# STM32.net
KiCad netlist of a schematic drawn in Altium Designer
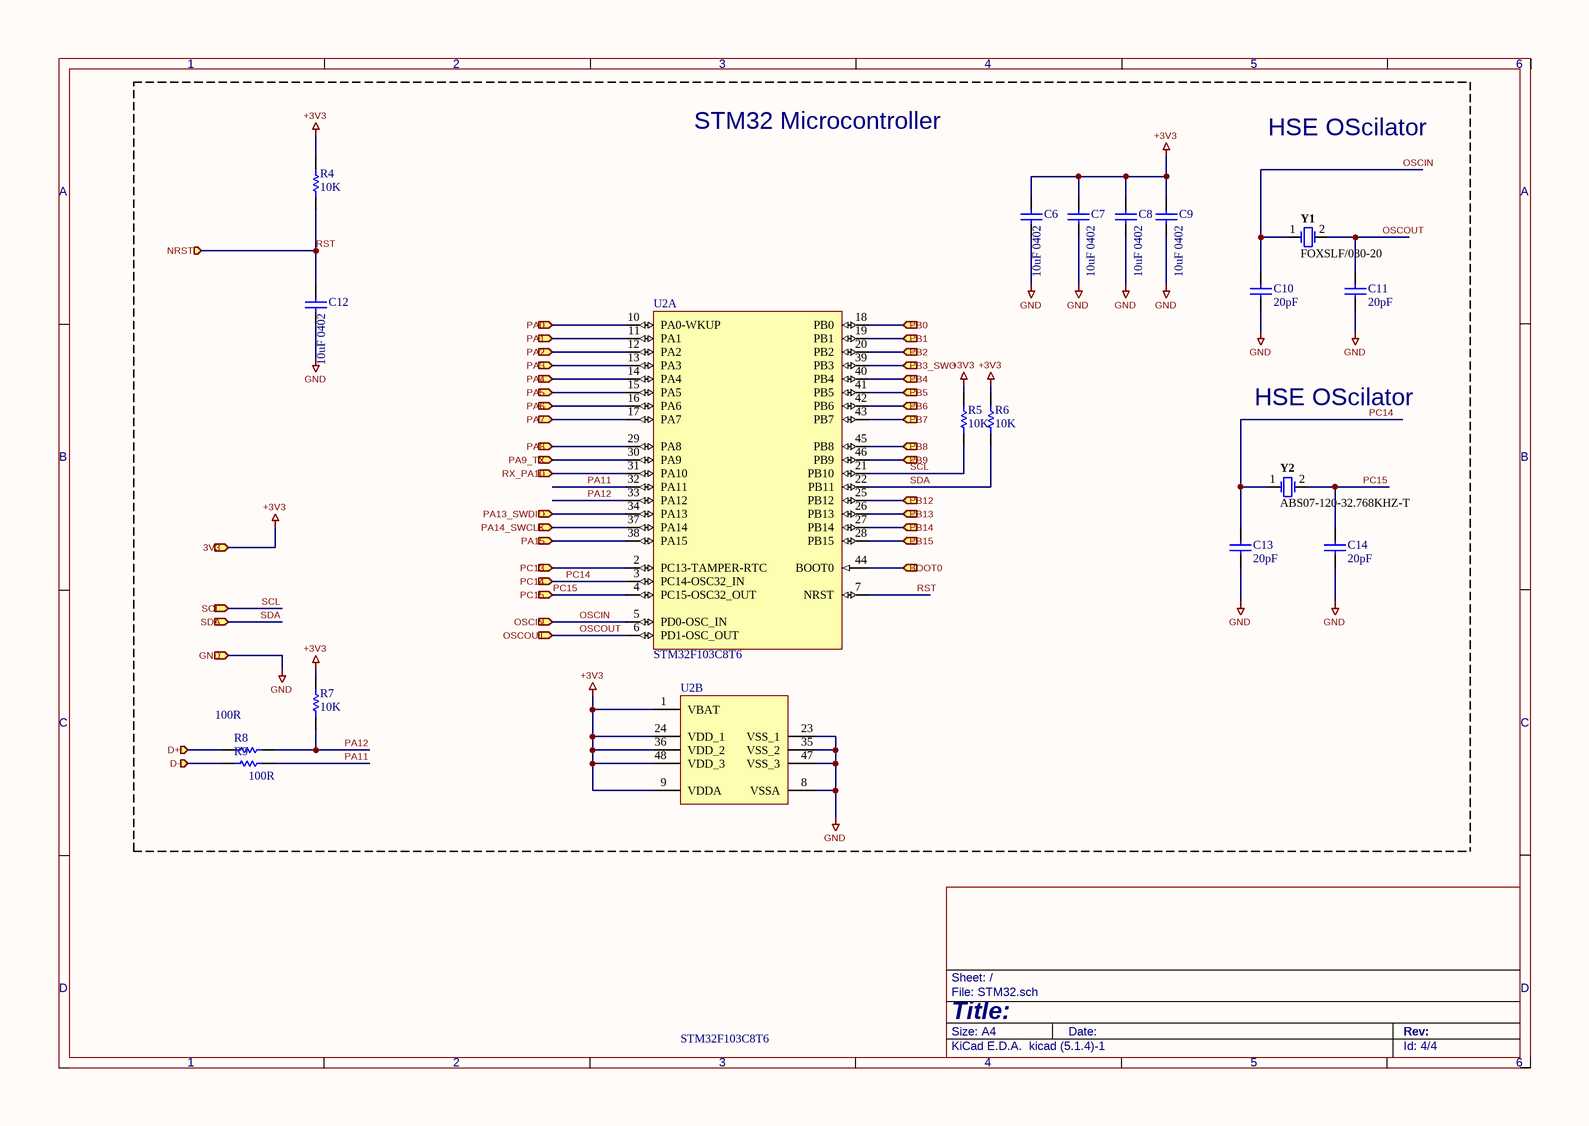
[diagram p0: STM32.SchDoc]

(export (version "E")
  (design (tool "Eeschema 10.0.6"))
  (components
    (comp (ref "C6")
      (value "10uF 0402")
      (footprint "CAPC1005X55X30ML05T10")
      (fields (field (name "MANUFACTURER") "Kemet") (field (name "PART NUMBER") "C0402C104J4RACTU"))
      (libsource (lib "Altium Content Vault") (part "CAP"))
    )
    (comp (ref "C7")
      (value "10uF 0402")
      (footprint "CAPC1005X55X30ML05T10")
      (fields (field (name "MANUFACTURER") "Kemet") (field (name "PART NUMBER") "C0402C104J4RACTU"))
      (libsource (lib "Altium Content Vault") (part "CAP"))
    )
    (comp (ref "C8")
      (value "10uF 0402")
      (footprint "CAPC1005X55X30ML05T10")
      (fields (field (name "MANUFACTURER") "Kemet") (field (name "PART NUMBER") "C0402C104J4RACTU"))
      (libsource (lib "Altium Content Vault") (part "CAP"))
    )
    (comp (ref "C9")
      (value "10uF 0402")
      (footprint "CAPC1005X55X30ML05T10")
      (fields (field (name "MANUFACTURER") "Kemet") (field (name "PART NUMBER") "C0402C104J4RACTU"))
      (libsource (lib "Altium Content Vault") (part "CAP"))
    )
    (comp (ref "C10")
      (value "20pF")
      (footprint "CAPC1005X56X25NL10T15")
      (fields
        (field (name "PART NUMBER") "04025A200JAT2A")
        (field (name "MANUFACTURER") "AVX Interconnect / Elco")
      )
      (libsource (lib "Altium Content Vault") (part "CAP"))
    )
    (comp (ref "C11")
      (value "20pF")
      (footprint "CAPC1005X56X25NL10T15")
      (fields
        (field (name "PART NUMBER") "04025A200JAT2A")
        (field (name "MANUFACTURER") "AVX Interconnect / Elco")
      )
      (libsource (lib "Altium Content Vault") (part "CAP"))
    )
    (comp (ref "C12")
      (value "10uF 0402")
      (footprint "CAPC1005X55X30ML05T10")
      (fields (field (name "MANUFACTURER") "Kemet") (field (name "PART NUMBER") "C0402C104J4RACTU"))
      (libsource (lib "Altium Content Vault") (part "CAP"))
    )
    (comp (ref "C13")
      (value "20pF")
      (footprint "CAPC1005X56X25NL10T15")
      (fields
        (field (name "PART NUMBER") "04025A200JAT2A")
        (field (name "MANUFACTURER") "AVX Interconnect / Elco")
      )
      (libsource (lib "Altium Content Vault") (part "CAP"))
    )
    (comp (ref "C14")
      (value "20pF")
      (footprint "CAPC1005X56X25NL10T15")
      (fields
        (field (name "PART NUMBER") "04025A200JAT2A")
        (field (name "MANUFACTURER") "AVX Interconnect / Elco")
      )
      (libsource (lib "Altium Content Vault") (part "CAP"))
    )
    (comp (ref "R4")
      (value "10K")
      (footprint "RESC1005X40X25NL05T05")
      (fields (field (name "MANUFACTURER") "Vishay Dale") (field (name "PART NUMBER") "CRCW0402330RFKED"))
      (libsource (lib "Altium Content Vault") (part "RES"))
    )
    (comp (ref "R5")
      (value "10K")
      (footprint "RESC1005X40X25NL05T05")
      (fields (field (name "MANUFACTURER") "Vishay Dale") (field (name "PART NUMBER") "CRCW0402330RFKED"))
      (libsource (lib "Altium Content Vault") (part "RES"))
    )
    (comp (ref "R6")
      (value "10K")
      (footprint "RESC1005X40X25NL05T05")
      (fields (field (name "MANUFACTURER") "Vishay Dale") (field (name "PART NUMBER") "CRCW0402330RFKED"))
      (libsource (lib "Altium Content Vault") (part "RES"))
    )
    (comp (ref "R7")
      (value "10K")
      (footprint "RESC1005X40X25NL05T05")
      (fields (field (name "MANUFACTURER") "Vishay Dale") (field (name "PART NUMBER") "CRCW0402330RFKED"))
      (libsource (lib "Altium Content Vault") (part "RES"))
    )
    (comp (ref "R8")
      (value "100R")
      (footprint "RESC1005X40X25NL05T05")
      (fields (field (name "MANUFACTURER") "Vishay Dale") (field (name "PART NUMBER") "CRCW0402330RFKED"))
      (libsource (lib "Altium Content Vault") (part "RES"))
    )
    (comp (ref "R9")
      (value "100R")
      (footprint "RESC1005X40X25NL05T05")
      (fields (field (name "MANUFACTURER") "Vishay Dale") (field (name "PART NUMBER") "CRCW0402330RFKED"))
      (libsource (lib "Altium Content Vault") (part "RES"))
    )
    (comp (ref "U2")
      (value "STM32F103C8T6")
      (footprint "STM-LQFP48_L")
      (libsource (lib "Altium Content Vault") (part "MC-ARM-STM32F103X8_B-SQ48"))
    )
    (comp (ref "Y1")
      (value "FOXSLF/080-20")
      (footprint "FOX-FOXSLF080-20")
      (description "Resistance Weld Thru-Hole Crystal, 8 MHz, -20 to 70 degC, 2-Pin THD, RoHS, Bulk")
      (libsource (lib "Altium Content Vault") (part "XTAL-1-2-2"))
    )
    (comp (ref "Y2")
      (value "ABS07-120-32.768KHZ-T")
      (footprint "ABRA-ABS07_A_V")
      (description "Tuning Fork Crystal, 32.768 KHz, +/- 20 ppm, -40 to 85 degC, 2-Pin SMD, RoHS, Tape and Reel")
      (fields (field (name "MANUFACTURER") "Abracon") (field (name "TOLERANCE") "20ppm"))
      (libsource (lib "Altium Content Vault") (part "XTAL-1-2-2"))
    )
  )
  (nets
    (net (code "1") (name "+3V3") (class "Default")
      (node (ref "C6") (pin "2") (pinfunction "2_2") (pintype "passive"))
      (node (ref "C7") (pin "2") (pinfunction "2_2") (pintype "passive"))
      (node (ref "C8") (pin "2") (pinfunction "2_2") (pintype "passive"))
      (node (ref "C9") (pin "2") (pinfunction "2_2") (pintype "passive"))
      (node (ref "R4") (pin "2") (pinfunction "2_2") (pintype "passive"))
      (node (ref "R5") (pin "2") (pinfunction "2_2") (pintype "passive"))
      (node (ref "R6") (pin "2") (pinfunction "2_2") (pintype "passive"))
      (node (ref "R7") (pin "2") (pinfunction "2_2") (pintype "passive"))
      (node (ref "U2") (pin "1") (pinfunction "VBAT_1") (pintype "power_in"))
      (node (ref "U2") (pin "24") (pinfunction "VDD_1_24") (pintype "power_in"))
      (node (ref "U2") (pin "36") (pinfunction "VDD_2_36") (pintype "power_in"))
      (node (ref "U2") (pin "48") (pinfunction "VDD_3_48") (pintype "power_in"))
      (node (ref "U2") (pin "9") (pinfunction "VDDA_9") (pintype "power_in"))
    )
    (net (code "2") (name "/BOOT0") (class "Default")
      (node (ref "U2") (pin "44") (pinfunction "BOOT0_44") (pintype "input"))
    )
    (net (code "3") (name "/D+") (class "Default")
      (node (ref "R8") (pin "2") (pinfunction "2_2") (pintype "passive"))
    )
    (net (code "4") (name "/D-") (class "Default")
      (node (ref "R9") (pin "2") (pinfunction "2_2") (pintype "passive"))
    )
    (net (code "5") (name "/OSCIN") (class "Default")
      (node (ref "C10") (pin "2") (pinfunction "2_2") (pintype "passive"))
      (node (ref "U2") (pin "5") (pinfunction "PD0-OSC_IN_5") (pintype "bidirectional"))
      (node (ref "Y1") (pin "1") (pinfunction "1_1") (pintype "passive"))
    )
    (net (code "6") (name "/OSCOUT") (class "Default")
      (node (ref "C11") (pin "2") (pinfunction "2_2") (pintype "passive"))
      (node (ref "U2") (pin "6") (pinfunction "PD1-OSC_OUT_6") (pintype "bidirectional"))
      (node (ref "Y1") (pin "2") (pinfunction "2_2") (pintype "passive"))
    )
    (net (code "7") (name "/PA0") (class "Default")
      (node (ref "U2") (pin "10") (pinfunction "PA0-WKUP_10") (pintype "bidirectional"))
    )
    (net (code "8") (name "/PA1") (class "Default")
      (node (ref "U2") (pin "11") (pinfunction "PA1_11") (pintype "bidirectional"))
    )
    (net (code "9") (name "/PA2") (class "Default")
      (node (ref "U2") (pin "12") (pinfunction "PA2_12") (pintype "bidirectional"))
    )
    (net (code "10") (name "/PA3") (class "Default")
      (node (ref "U2") (pin "13") (pinfunction "PA3_13") (pintype "bidirectional"))
    )
    (net (code "11") (name "/PA4") (class "Default")
      (node (ref "U2") (pin "14") (pinfunction "PA4_14") (pintype "bidirectional"))
    )
    (net (code "12") (name "/PA5") (class "Default")
      (node (ref "U2") (pin "15") (pinfunction "PA5_15") (pintype "bidirectional"))
    )
    (net (code "13") (name "/PA6") (class "Default")
      (node (ref "U2") (pin "16") (pinfunction "PA6_16") (pintype "bidirectional"))
    )
    (net (code "14") (name "/PA7") (class "Default")
      (node (ref "U2") (pin "17") (pinfunction "PA7_17") (pintype "bidirectional"))
    )
    (net (code "15") (name "/PA8") (class "Default")
      (node (ref "U2") (pin "29") (pinfunction "PA8_29") (pintype "bidirectional"))
    )
    (net (code "16") (name "/PA9_TX") (class "Default")
      (node (ref "U2") (pin "30") (pinfunction "PA9_30") (pintype "bidirectional"))
    )
    (net (code "17") (name "/PA11") (class "Default")
      (node (ref "R9") (pin "1") (pinfunction "1_1") (pintype "passive"))
      (node (ref "U2") (pin "32") (pinfunction "PA11_32") (pintype "bidirectional"))
    )
    (net (code "18") (name "/PA12") (class "Default")
      (node (ref "R7") (pin "1") (pinfunction "1_1") (pintype "passive"))
      (node (ref "R8") (pin "1") (pinfunction "1_1") (pintype "passive"))
      (node (ref "U2") (pin "33") (pinfunction "PA12_33") (pintype "bidirectional"))
    )
    (net (code "19") (name "/PA13_SWDIO") (class "Default")
      (node (ref "U2") (pin "34") (pinfunction "PA13_34") (pintype "bidirectional"))
    )
    (net (code "20") (name "/PA14_SWCLK") (class "Default")
      (node (ref "U2") (pin "37") (pinfunction "PA14_37") (pintype "bidirectional"))
    )
    (net (code "21") (name "/PA15") (class "Default")
      (node (ref "U2") (pin "38") (pinfunction "PA15_38") (pintype "bidirectional"))
    )
    (net (code "22") (name "/PB0") (class "Default")
      (node (ref "U2") (pin "18") (pinfunction "PB0_18") (pintype "bidirectional"))
    )
    (net (code "23") (name "/PB1") (class "Default")
      (node (ref "U2") (pin "19") (pinfunction "PB1_19") (pintype "bidirectional"))
    )
    (net (code "24") (name "/PB2") (class "Default")
      (node (ref "U2") (pin "20") (pinfunction "PB2_20") (pintype "bidirectional"))
    )
    (net (code "25") (name "/PB3_SWO") (class "Default")
      (node (ref "U2") (pin "39") (pinfunction "PB3_39") (pintype "bidirectional"))
    )
    (net (code "26") (name "/PB4") (class "Default")
      (node (ref "U2") (pin "40") (pinfunction "PB4_40") (pintype "bidirectional"))
    )
    (net (code "27") (name "/PB5") (class "Default")
      (node (ref "U2") (pin "41") (pinfunction "PB5_41") (pintype "bidirectional"))
    )
    (net (code "28") (name "/PB6") (class "Default")
      (node (ref "U2") (pin "42") (pinfunction "PB6_42") (pintype "bidirectional"))
    )
    (net (code "29") (name "/PB7") (class "Default")
      (node (ref "U2") (pin "43") (pinfunction "PB7_43") (pintype "bidirectional"))
    )
    (net (code "30") (name "/PB8") (class "Default")
      (node (ref "U2") (pin "45") (pinfunction "PB8_45") (pintype "bidirectional"))
    )
    (net (code "31") (name "/PB9") (class "Default")
      (node (ref "U2") (pin "46") (pinfunction "PB9_46") (pintype "bidirectional"))
    )
    (net (code "32") (name "/PB12") (class "Default")
      (node (ref "U2") (pin "25") (pinfunction "PB12_25") (pintype "bidirectional"))
    )
    (net (code "33") (name "/PB13") (class "Default")
      (node (ref "U2") (pin "26") (pinfunction "PB13_26") (pintype "bidirectional"))
    )
    (net (code "34") (name "/PB14") (class "Default")
      (node (ref "U2") (pin "27") (pinfunction "PB14_27") (pintype "bidirectional"))
    )
    (net (code "35") (name "/PB15") (class "Default")
      (node (ref "U2") (pin "28") (pinfunction "PB15_28") (pintype "bidirectional"))
    )
    (net (code "36") (name "/PC13") (class "Default")
      (node (ref "U2") (pin "2") (pinfunction "PC13-TAMPER-RTC_2") (pintype "bidirectional"))
    )
    (net (code "37") (name "/PC14") (class "Default")
      (node (ref "C13") (pin "2") (pinfunction "2_2") (pintype "passive"))
      (node (ref "U2") (pin "3") (pinfunction "PC14-OSC32_IN_3") (pintype "bidirectional"))
      (node (ref "Y2") (pin "1") (pinfunction "1_1") (pintype "passive"))
    )
    (net (code "38") (name "/PC15") (class "Default")
      (node (ref "C14") (pin "2") (pinfunction "2_2") (pintype "passive"))
      (node (ref "U2") (pin "4") (pinfunction "PC15-OSC32_OUT_4") (pintype "bidirectional"))
      (node (ref "Y2") (pin "2") (pinfunction "2_2") (pintype "passive"))
    )
    (net (code "39") (name "/RST") (class "Default")
      (node (ref "C12") (pin "2") (pinfunction "2_2") (pintype "passive"))
      (node (ref "R4") (pin "1") (pinfunction "1_1") (pintype "passive"))
      (node (ref "U2") (pin "7") (pinfunction "NRST_7") (pintype "bidirectional"))
    )
    (net (code "40") (name "/RX_PA10") (class "Default")
      (node (ref "U2") (pin "31") (pinfunction "PA10_31") (pintype "bidirectional"))
    )
    (net (code "41") (name "/SCL") (class "Default")
      (node (ref "R5") (pin "1") (pinfunction "1_1") (pintype "passive"))
      (node (ref "U2") (pin "21") (pinfunction "PB10_21") (pintype "bidirectional"))
    )
    (net (code "42") (name "/SDA") (class "Default")
      (node (ref "R6") (pin "1") (pinfunction "1_1") (pintype "passive"))
      (node (ref "U2") (pin "22") (pinfunction "PB11_22") (pintype "bidirectional"))
    )
    (net (code "43") (name "GND") (class "Default")
      (node (ref "C10") (pin "1") (pinfunction "1_1") (pintype "passive"))
      (node (ref "C11") (pin "1") (pinfunction "1_1") (pintype "passive"))
      (node (ref "C12") (pin "1") (pinfunction "1_1") (pintype "passive"))
      (node (ref "C13") (pin "1") (pinfunction "1_1") (pintype "passive"))
      (node (ref "C14") (pin "1") (pinfunction "1_1") (pintype "passive"))
      (node (ref "C6") (pin "1") (pinfunction "1_1") (pintype "passive"))
      (node (ref "C7") (pin "1") (pinfunction "1_1") (pintype "passive"))
      (node (ref "C8") (pin "1") (pinfunction "1_1") (pintype "passive"))
      (node (ref "C9") (pin "1") (pinfunction "1_1") (pintype "passive"))
      (node (ref "U2") (pin "23") (pinfunction "VSS_1_23") (pintype "power_in"))
      (node (ref "U2") (pin "35") (pinfunction "VSS_2_35") (pintype "power_in"))
      (node (ref "U2") (pin "47") (pinfunction "VSS_3_47") (pintype "power_in"))
      (node (ref "U2") (pin "8") (pinfunction "VSSA_8") (pintype "power_in"))
    )
  )
)
